# LiDAR.net
KiCad netlist of a schematic drawn in EAGLE
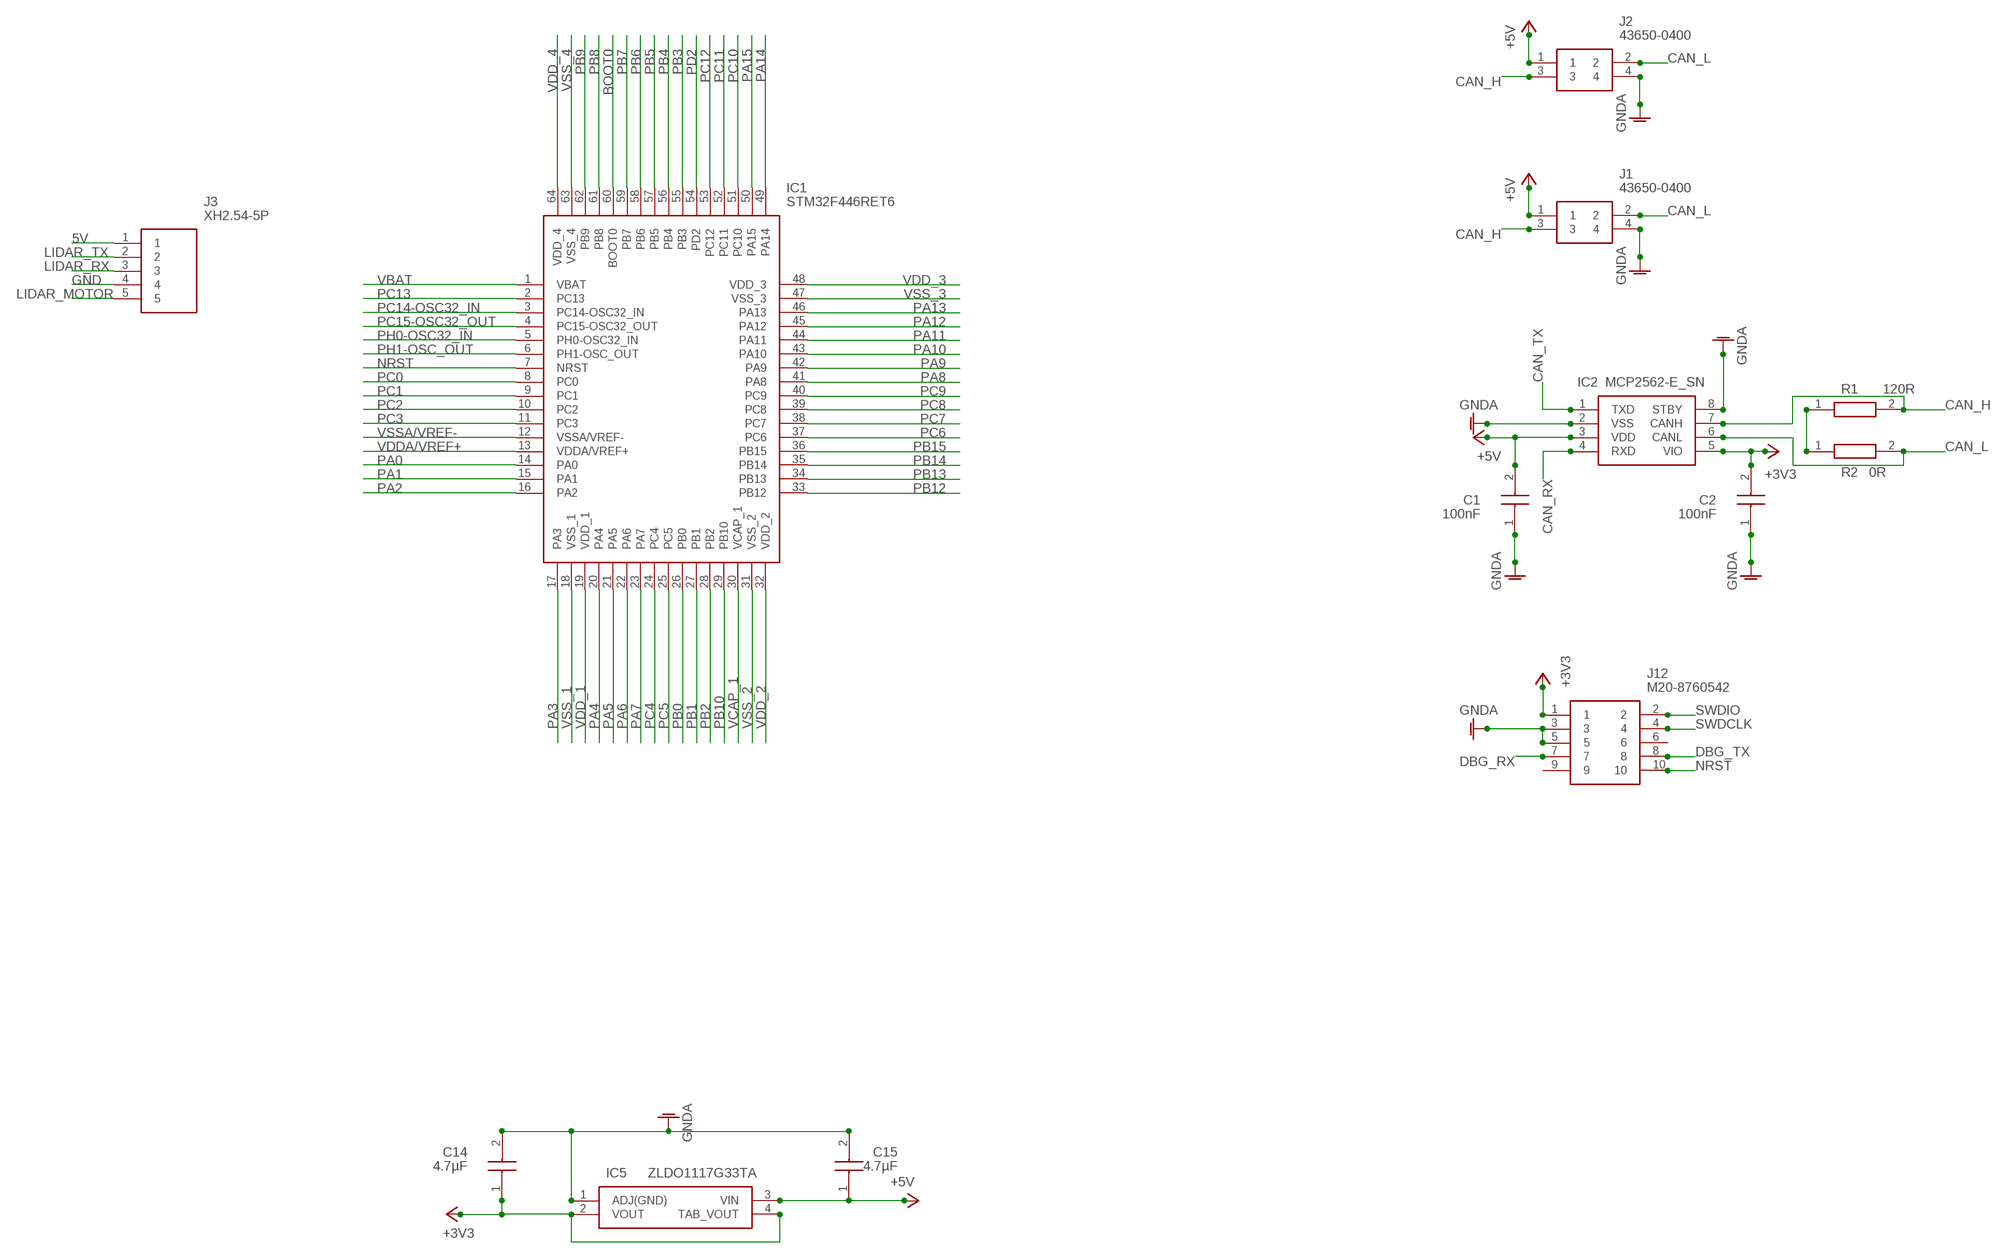
[diagram p0: schematic, sheet 1]

(export (version "E")
  (design (tool "Eeschema 10.0.6"))
  (components
    (comp (ref "C1")
      (value "100nF")
      (footprint "eagle-import:CAPC1608X90N")
      (fields
        (field (name "MANUFACTURER_PART_NUMBER") "06035C104K4T2A")
        (field (name "MOUSER_PART_NUMBER") "581-06035C104K4")
        (field (name "RS_PART_NUMBER") "6983251P")
      )
      (libsource (lib "eagle-import") (part "06035C104K4T2A"))
    )
    (comp (ref "C2")
      (value "100nF")
      (footprint "eagle-import:CAPC1608X90N")
      (fields
        (field (name "MANUFACTURER_PART_NUMBER") "06035C104K4T2A")
        (field (name "MOUSER_PART_NUMBER") "581-06035C104K4")
        (field (name "RS_PART_NUMBER") "6983251P")
      )
      (libsource (lib "eagle-import") (part "06035C104K4T2A"))
    )
    (comp (ref "C14")
      (value "4.7µF")
      (footprint "eagle-import:CAPC2012X145N")
      (fields
        (field (name "MANUFACTURER_PART_NUMBER") "GRM21BR61E475KA12L")
        (field (name "MOUSER_PART_NUMBER") "81-GRM21BR61E475KA12")
        (field (name "RS_PART_NUMBER") "7236057")
      )
      (libsource (lib "eagle-import") (part "GRM21BR61E475KA12L"))
    )
    (comp (ref "C15")
      (value "4.7µF")
      (footprint "eagle-import:CAPC2012X145N")
      (fields
        (field (name "MANUFACTURER_PART_NUMBER") "GRM21BR61E475KA12L")
        (field (name "MOUSER_PART_NUMBER") "81-GRM21BR61E475KA12")
        (field (name "RS_PART_NUMBER") "7236057")
      )
      (libsource (lib "eagle-import") (part "GRM21BR61E475KA12L"))
    )
    (comp (ref "IC1")
      (value "STM32F446RET6")
      (footprint "eagle-import:QFP50P1200X1200X160-64N")
      (fields
        (field (name "MOUSER_PART_NUMBER") "511-STM32F446RET6")
        (field (name "RS_PART_NUMBER") "1106621P")
      )
      (libsource (lib "eagle-import") (part "STM32F446RET6"))
    )
    (comp (ref "IC2")
      (value "MCP2562-E_SN")
      (footprint "eagle-import:SOIC127P600X175-8N")
      (fields
        (field (name "MANUFACTURER_PART_NUMBER") "MCP2562-E/SN")
        (field (name "MOUSER_PART_NUMBER") "579-MCP2562-E/SN")
        (field (name "RS_PART_NUMBER") "7990228P")
      )
      (libsource (lib "eagle-import") (part "MCP2562-E_SN"))
    )
    (comp (ref "IC5")
      (value "ZLDO1117G33TA")
      (footprint "eagle-import:SOT230P700X180-4N")
      (fields
        (field (name "MOUSER_PART_NUMBER") "522-ZLDO1117G33TA")
        (field (name "RS_PART_NUMBER") "7515183P")
      )
      (libsource (lib "eagle-import") (part "ZLDO1117G33TA"))
    )
    (comp (ref "J1")
      (value "43650-0400")
      (footprint "eagle-import:436500400")
      (fields (field (name "MOUSER_PART_NUMBER") "538-43650-0400") (field (name "RS_PART_NUMBER") "6704733P"))
      (libsource (lib "eagle-import") (part "43650-0400"))
    )
    (comp (ref "J2")
      (value "43650-0400")
      (footprint "eagle-import:436500400")
      (fields (field (name "MOUSER_PART_NUMBER") "538-43650-0400") (field (name "RS_PART_NUMBER") "6704733P"))
      (libsource (lib "eagle-import") (part "43650-0400"))
    )
    (comp (ref "J3")
      (value "XH2.54-5P")
      (footprint "eagle-import:SHDR5W64P0X250_1X5_1490X575X70")
      (libsource (lib "eagle-import") (part "XH2.54-5P"))
    )
    (comp (ref "J12")
      (value "M20-8760542")
      (footprint "eagle-import:M208760542")
      (fields
        (field (name "MOUSER_PART_NUMBER") "855-M20-8760542")
        (field (name "RS_PART_NUMBER") "6812893P")
      )
      (libsource (lib "eagle-import") (part "M20-8760542"))
    )
    (comp (ref "R1")
      (value "120R")
      (footprint "eagle-import:RESC1608X50N")
      (fields
        (field (name "MANUFACTURER_PART_NUMBER") "CRCW0603120RFKEA")
        (field (name "MOUSER_PART_NUMBER") "71-CRCW0603-120-E3")
        (field (name "RS_PART_NUMBER") "6789718")
      )
      (libsource (lib "eagle-import") (part "CRCW0603120RFKEA"))
    )
    (comp (ref "R2")
      (value "0R")
      (footprint "eagle-import:RESC1608X55N")
      (fields (field (name "MANUFACTURER_PART_NUMBER") "RK73Z1JTTDB"))
      (libsource (lib "eagle-import") (part "RK73Z1JTTDB"))
    )
  )
  (nets
    (net (code "1") (name "+3V3") (class "Default")
      (node (ref "C14") (pin "1") (pinfunction "1_1") (pintype "bidirectional"))
      (node (ref "C2") (pin "2") (pinfunction "2_2") (pintype "bidirectional"))
      (node (ref "IC2") (pin "5") (pinfunction "VIO_5") (pintype "bidirectional"))
      (node (ref "IC5") (pin "2") (pinfunction "VOUT_2") (pintype "output"))
      (node (ref "IC5") (pin "4") (pinfunction "TAB_VOUT_4") (pintype "output"))
      (node (ref "J12") (pin "1") (pinfunction "1_1") (pintype "bidirectional"))
    )
    (net (code "2") (name "+5V") (class "Default")
      (node (ref "C1") (pin "2") (pinfunction "2_2") (pintype "bidirectional"))
      (node (ref "C15") (pin "1") (pinfunction "1_1") (pintype "bidirectional"))
      (node (ref "IC2") (pin "3") (pinfunction "VDD_3") (pintype "bidirectional"))
      (node (ref "IC5") (pin "3") (pinfunction "VIN_3") (pintype "input"))
      (node (ref "J1") (pin "1") (pinfunction "1_1") (pintype "bidirectional"))
      (node (ref "J2") (pin "1") (pinfunction "1_1") (pintype "bidirectional"))
    )
    (net (code "3") (name "/5V") (class "Default")
      (node (ref "J3") (pin "1") (pinfunction "1_1") (pintype "bidirectional"))
    )
    (net (code "4") (name "/BOOT0") (class "Default")
      (node (ref "IC1") (pin "60") (pinfunction "BOOT0_60") (pintype "bidirectional"))
    )
    (net (code "5") (name "/CAN_H") (class "Default")
      (node (ref "IC2") (pin "7") (pinfunction "CANH_7") (pintype "bidirectional"))
      (node (ref "J1") (pin "3") (pinfunction "3_3") (pintype "bidirectional"))
      (node (ref "J2") (pin "3") (pinfunction "3_3") (pintype "bidirectional"))
      (node (ref "R1") (pin "2") (pinfunction "2_2") (pintype "bidirectional"))
    )
    (net (code "6") (name "/CAN_L") (class "Default")
      (node (ref "IC2") (pin "6") (pinfunction "CANL_6") (pintype "bidirectional"))
      (node (ref "J1") (pin "2") (pinfunction "2_2") (pintype "bidirectional"))
      (node (ref "J2") (pin "2") (pinfunction "2_2") (pintype "bidirectional"))
      (node (ref "R2") (pin "2") (pinfunction "2_2") (pintype "bidirectional"))
    )
    (net (code "7") (name "/CAN_RX") (class "Default")
      (node (ref "IC2") (pin "4") (pinfunction "RXD_4") (pintype "bidirectional"))
    )
    (net (code "8") (name "/CAN_TX") (class "Default")
      (node (ref "IC2") (pin "1") (pinfunction "TXD_1") (pintype "bidirectional"))
    )
    (net (code "9") (name "/DBG_RX") (class "Default")
      (node (ref "J12") (pin "7") (pinfunction "7_7") (pintype "bidirectional"))
    )
    (net (code "10") (name "/DBG_TX") (class "Default")
      (node (ref "J12") (pin "8") (pinfunction "8_8") (pintype "bidirectional"))
    )
    (net (code "11") (name "/GND") (class "Default")
      (node (ref "J3") (pin "4") (pinfunction "4_4") (pintype "bidirectional"))
    )
    (net (code "12") (name "/LIDAR_MOTOR") (class "Default")
      (node (ref "J3") (pin "5") (pinfunction "5_5") (pintype "bidirectional"))
    )
    (net (code "13") (name "/LIDAR_RX") (class "Default")
      (node (ref "J3") (pin "3") (pinfunction "3_3") (pintype "bidirectional"))
    )
    (net (code "14") (name "/LIDAR_TX") (class "Default")
      (node (ref "J3") (pin "2") (pinfunction "2_2") (pintype "bidirectional"))
    )
    (net (code "15") (name "/NRST") (class "Default")
      (node (ref "IC1") (pin "7") (pinfunction "NRST_7") (pintype "bidirectional"))
      (node (ref "J12") (pin "10") (pinfunction "10_10") (pintype "bidirectional"))
    )
    (net (code "16") (name "/PA0") (class "Default")
      (node (ref "IC1") (pin "14") (pinfunction "PA0_14") (pintype "bidirectional"))
    )
    (net (code "17") (name "/PA1") (class "Default")
      (node (ref "IC1") (pin "15") (pinfunction "PA1_15") (pintype "bidirectional"))
    )
    (net (code "18") (name "/PA2") (class "Default")
      (node (ref "IC1") (pin "16") (pinfunction "PA2_16") (pintype "bidirectional"))
    )
    (net (code "19") (name "/PA3") (class "Default")
      (node (ref "IC1") (pin "17") (pinfunction "PA3_17") (pintype "bidirectional"))
    )
    (net (code "20") (name "/PA4") (class "Default")
      (node (ref "IC1") (pin "20") (pinfunction "PA4_20") (pintype "bidirectional"))
    )
    (net (code "21") (name "/PA5") (class "Default")
      (node (ref "IC1") (pin "21") (pinfunction "PA5_21") (pintype "bidirectional"))
    )
    (net (code "22") (name "/PA6") (class "Default")
      (node (ref "IC1") (pin "22") (pinfunction "PA6_22") (pintype "bidirectional"))
    )
    (net (code "23") (name "/PA7") (class "Default")
      (node (ref "IC1") (pin "23") (pinfunction "PA7_23") (pintype "bidirectional"))
    )
    (net (code "24") (name "/PA8") (class "Default")
      (node (ref "IC1") (pin "41") (pinfunction "PA8_41") (pintype "bidirectional"))
    )
    (net (code "25") (name "/PA9") (class "Default")
      (node (ref "IC1") (pin "42") (pinfunction "PA9_42") (pintype "bidirectional"))
    )
    (net (code "26") (name "/PA10") (class "Default")
      (node (ref "IC1") (pin "43") (pinfunction "PA10_43") (pintype "bidirectional"))
    )
    (net (code "27") (name "/PA11") (class "Default")
      (node (ref "IC1") (pin "44") (pinfunction "PA11_44") (pintype "bidirectional"))
    )
    (net (code "28") (name "/PA12") (class "Default")
      (node (ref "IC1") (pin "45") (pinfunction "PA12_45") (pintype "bidirectional"))
    )
    (net (code "29") (name "/PA13") (class "Default")
      (node (ref "IC1") (pin "46") (pinfunction "PA13_46") (pintype "bidirectional"))
    )
    (net (code "30") (name "/PA14") (class "Default")
      (node (ref "IC1") (pin "49") (pinfunction "PA14_49") (pintype "bidirectional"))
    )
    (net (code "31") (name "/PA15") (class "Default")
      (node (ref "IC1") (pin "50") (pinfunction "PA15_50") (pintype "bidirectional"))
    )
    (net (code "32") (name "/PB0") (class "Default")
      (node (ref "IC1") (pin "26") (pinfunction "PB0_26") (pintype "bidirectional"))
    )
    (net (code "33") (name "/PB1") (class "Default")
      (node (ref "IC1") (pin "27") (pinfunction "PB1_27") (pintype "bidirectional"))
    )
    (net (code "34") (name "/PB2") (class "Default")
      (node (ref "IC1") (pin "28") (pinfunction "PB2_28") (pintype "bidirectional"))
    )
    (net (code "35") (name "/PB3") (class "Default")
      (node (ref "IC1") (pin "55") (pinfunction "PB3_55") (pintype "bidirectional"))
    )
    (net (code "36") (name "/PB4") (class "Default")
      (node (ref "IC1") (pin "56") (pinfunction "PB4_56") (pintype "bidirectional"))
    )
    (net (code "37") (name "/PB5") (class "Default")
      (node (ref "IC1") (pin "57") (pinfunction "PB5_57") (pintype "bidirectional"))
    )
    (net (code "38") (name "/PB6") (class "Default")
      (node (ref "IC1") (pin "58") (pinfunction "PB6_58") (pintype "bidirectional"))
    )
    (net (code "39") (name "/PB7") (class "Default")
      (node (ref "IC1") (pin "59") (pinfunction "PB7_59") (pintype "bidirectional"))
    )
    (net (code "40") (name "/PB8") (class "Default")
      (node (ref "IC1") (pin "61") (pinfunction "PB8_61") (pintype "bidirectional"))
    )
    (net (code "41") (name "/PB9") (class "Default")
      (node (ref "IC1") (pin "62") (pinfunction "PB9_62") (pintype "bidirectional"))
    )
    (net (code "42") (name "/PB10") (class "Default")
      (node (ref "IC1") (pin "29") (pinfunction "PB10_29") (pintype "bidirectional"))
    )
    (net (code "43") (name "/PB12") (class "Default")
      (node (ref "IC1") (pin "33") (pinfunction "PB12_33") (pintype "bidirectional"))
    )
    (net (code "44") (name "/PB13") (class "Default")
      (node (ref "IC1") (pin "34") (pinfunction "PB13_34") (pintype "bidirectional"))
    )
    (net (code "45") (name "/PB14") (class "Default")
      (node (ref "IC1") (pin "35") (pinfunction "PB14_35") (pintype "bidirectional"))
    )
    (net (code "46") (name "/PB15") (class "Default")
      (node (ref "IC1") (pin "36") (pinfunction "PB15_36") (pintype "bidirectional"))
    )
    (net (code "47") (name "/PC0") (class "Default")
      (node (ref "IC1") (pin "8") (pinfunction "PC0_8") (pintype "bidirectional"))
    )
    (net (code "48") (name "/PC1") (class "Default")
      (node (ref "IC1") (pin "9") (pinfunction "PC1_9") (pintype "bidirectional"))
    )
    (net (code "49") (name "/PC2") (class "Default")
      (node (ref "IC1") (pin "10") (pinfunction "PC2_10") (pintype "bidirectional"))
    )
    (net (code "50") (name "/PC3") (class "Default")
      (node (ref "IC1") (pin "11") (pinfunction "PC3_11") (pintype "bidirectional"))
    )
    (net (code "51") (name "/PC4") (class "Default")
      (node (ref "IC1") (pin "24") (pinfunction "PC4_24") (pintype "bidirectional"))
    )
    (net (code "52") (name "/PC5") (class "Default")
      (node (ref "IC1") (pin "25") (pinfunction "PC5_25") (pintype "bidirectional"))
    )
    (net (code "53") (name "/PC6") (class "Default")
      (node (ref "IC1") (pin "37") (pinfunction "PC6_37") (pintype "bidirectional"))
    )
    (net (code "54") (name "/PC7") (class "Default")
      (node (ref "IC1") (pin "38") (pinfunction "PC7_38") (pintype "bidirectional"))
    )
    (net (code "55") (name "/PC8") (class "Default")
      (node (ref "IC1") (pin "39") (pinfunction "PC8_39") (pintype "bidirectional"))
    )
    (net (code "56") (name "/PC9") (class "Default")
      (node (ref "IC1") (pin "40") (pinfunction "PC9_40") (pintype "bidirectional"))
    )
    (net (code "57") (name "/PC10") (class "Default")
      (node (ref "IC1") (pin "51") (pinfunction "PC10_51") (pintype "bidirectional"))
    )
    (net (code "58") (name "/PC11") (class "Default")
      (node (ref "IC1") (pin "52") (pinfunction "PC11_52") (pintype "bidirectional"))
    )
    (net (code "59") (name "/PC12") (class "Default")
      (node (ref "IC1") (pin "53") (pinfunction "PC12_53") (pintype "bidirectional"))
    )
    (net (code "60") (name "/PC13") (class "Default")
      (node (ref "IC1") (pin "2") (pinfunction "PC13_2") (pintype "bidirectional"))
    )
    (net (code "61") (name "/PC14-OSC32_IN") (class "Default")
      (node (ref "IC1") (pin "3") (pinfunction "PC14-OSC32_IN_3") (pintype "bidirectional"))
    )
    (net (code "62") (name "/PC15-OSC32_OUT") (class "Default")
      (node (ref "IC1") (pin "4") (pinfunction "PC15-OSC32_OUT_4") (pintype "bidirectional"))
    )
    (net (code "63") (name "/PD2") (class "Default")
      (node (ref "IC1") (pin "54") (pinfunction "PD2_54") (pintype "bidirectional"))
    )
    (net (code "64") (name "/PH0-OSC32_IN") (class "Default")
      (node (ref "IC1") (pin "5") (pinfunction "PH0-OSC32_IN_5") (pintype "bidirectional"))
    )
    (net (code "65") (name "/PH1-OSC_OUT") (class "Default")
      (node (ref "IC1") (pin "6") (pinfunction "PH1-OSC_OUT_6") (pintype "bidirectional"))
    )
    (net (code "66") (name "/SWDCLK") (class "Default")
      (node (ref "J12") (pin "4") (pinfunction "4_4") (pintype "bidirectional"))
    )
    (net (code "67") (name "/SWDIO") (class "Default")
      (node (ref "J12") (pin "2") (pinfunction "2_2") (pintype "bidirectional"))
    )
    (net (code "68") (name "/VBAT") (class "Default")
      (node (ref "IC1") (pin "1") (pinfunction "VBAT_1") (pintype "bidirectional"))
    )
    (net (code "69") (name "/VCAP_1") (class "Default")
      (node (ref "IC1") (pin "30") (pinfunction "VCAP_1_30") (pintype "bidirectional"))
    )
    (net (code "70") (name "/VDDA{slash}VREF+") (class "Default")
      (node (ref "IC1") (pin "13") (pinfunction "VDDA/VREF+_13") (pintype "bidirectional"))
    )
    (net (code "71") (name "/VDD_1") (class "Default")
      (node (ref "IC1") (pin "19") (pinfunction "VDD_1_19") (pintype "bidirectional"))
    )
    (net (code "72") (name "/VDD_2") (class "Default")
      (node (ref "IC1") (pin "32") (pinfunction "VDD_2_32") (pintype "bidirectional"))
    )
    (net (code "73") (name "/VDD_3") (class "Default")
      (node (ref "IC1") (pin "48") (pinfunction "VDD_3_48") (pintype "bidirectional"))
    )
    (net (code "74") (name "/VDD_4") (class "Default")
      (node (ref "IC1") (pin "64") (pinfunction "VDD_4_64") (pintype "bidirectional"))
    )
    (net (code "75") (name "/VSSA{slash}VREF-") (class "Default")
      (node (ref "IC1") (pin "12") (pinfunction "VSSA/VREF-_12") (pintype "bidirectional"))
    )
    (net (code "76") (name "/VSS_1") (class "Default")
      (node (ref "IC1") (pin "18") (pinfunction "VSS_1_18") (pintype "bidirectional"))
    )
    (net (code "77") (name "/VSS_2") (class "Default")
      (node (ref "IC1") (pin "31") (pinfunction "VSS_2_31") (pintype "bidirectional"))
    )
    (net (code "78") (name "/VSS_3") (class "Default")
      (node (ref "IC1") (pin "47") (pinfunction "VSS_3_47") (pintype "bidirectional"))
    )
    (net (code "79") (name "/VSS_4") (class "Default")
      (node (ref "IC1") (pin "63") (pinfunction "VSS_4_63") (pintype "bidirectional"))
    )
    (net (code "80") (name "GNDA") (class "Default")
      (node (ref "C1") (pin "1") (pinfunction "1_1") (pintype "bidirectional"))
      (node (ref "C14") (pin "2") (pinfunction "2_2") (pintype "bidirectional"))
      (node (ref "C15") (pin "2") (pinfunction "2_2") (pintype "bidirectional"))
      (node (ref "C2") (pin "1") (pinfunction "1_1") (pintype "bidirectional"))
      (node (ref "IC2") (pin "2") (pinfunction "VSS_2") (pintype "bidirectional"))
      (node (ref "IC2") (pin "8") (pinfunction "STBY_8") (pintype "bidirectional"))
      (node (ref "IC5") (pin "1") (pinfunction "ADJ(GND)_1") (pintype "power_in"))
      (node (ref "J1") (pin "4") (pinfunction "4_4") (pintype "bidirectional"))
      (node (ref "J12") (pin "3") (pinfunction "3_3") (pintype "bidirectional"))
      (node (ref "J12") (pin "5") (pinfunction "5_5") (pintype "bidirectional"))
      (node (ref "J2") (pin "4") (pinfunction "4_4") (pintype "bidirectional"))
    )
    (net (code "81") (name "Net-(R1-Pad1)") (class "Default")
      (node (ref "R1") (pin "1") (pinfunction "1_1") (pintype "bidirectional"))
      (node (ref "R2") (pin "1") (pinfunction "1_1") (pintype "bidirectional"))
    )
    (net (code "82") (name "unconnected-(J12-Pad6)") (class "Default")
      (node (ref "J12") (pin "6") (pinfunction "6_6") (pintype "bidirectional"))
    )
    (net (code "83") (name "unconnected-(J12-Pad9)") (class "Default")
      (node (ref "J12") (pin "9") (pinfunction "9_9") (pintype "bidirectional"))
    )
  )
)
